# KX1_DB_PWR.net
KiCad netlist of a schematic drawn in Altium Designer
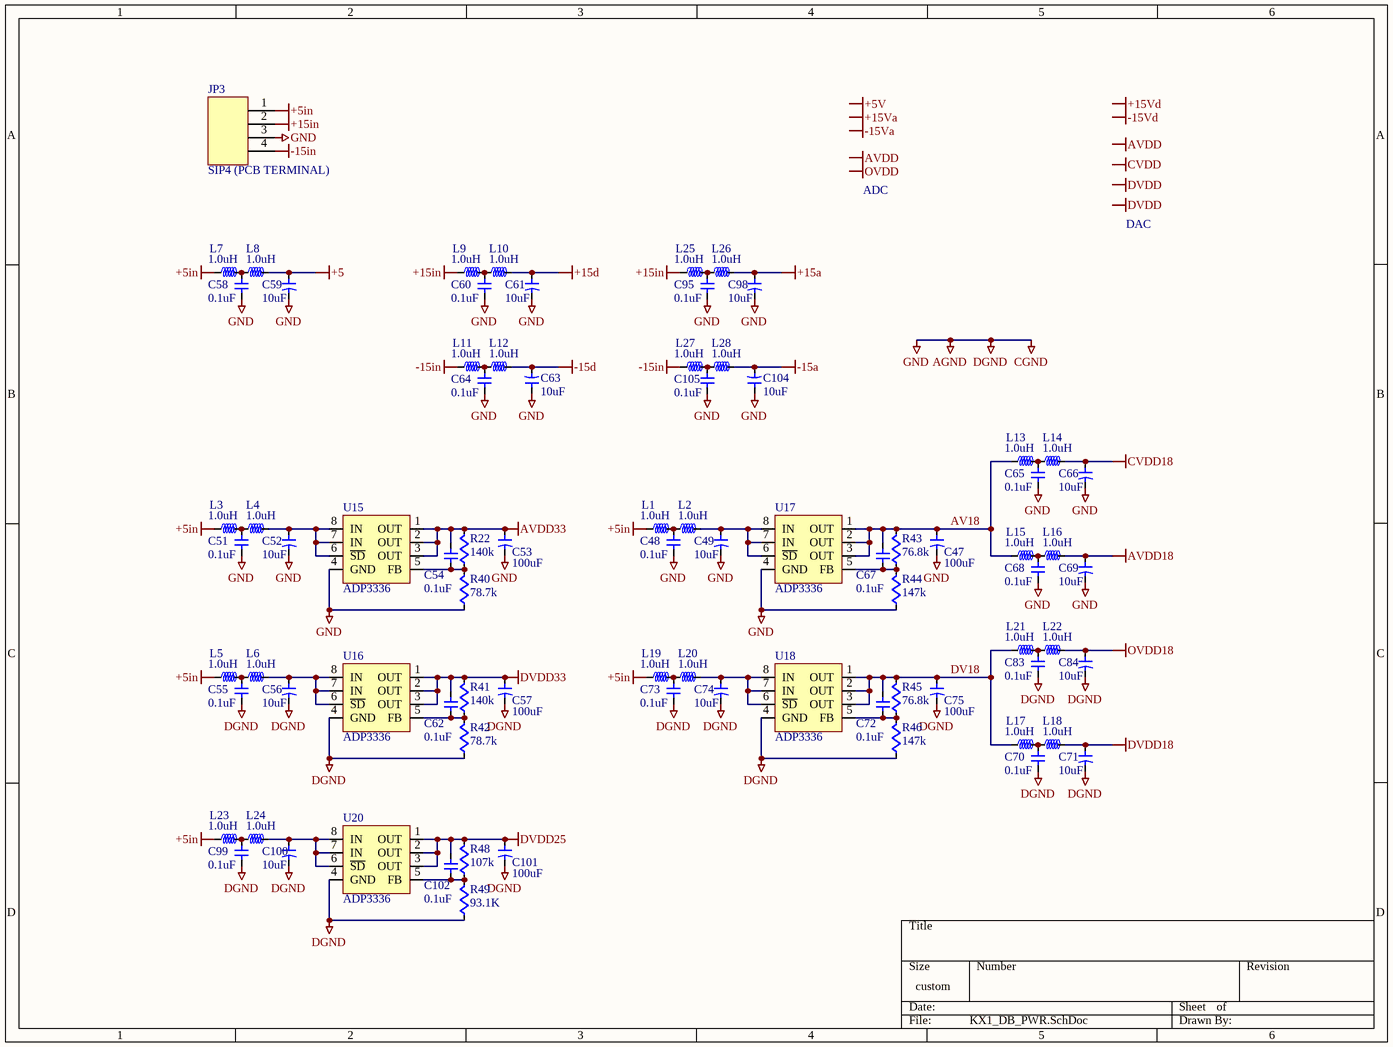
[diagram p0: KX1_DB_PWR.SchDoc]

(export (version "E")
  (design (tool "Eeschema 10.0.6"))
  (components
    (comp (ref "C47")
      (value "100uF")
      (footprint "1206")
      (description "capacitor")
      (fields
        (field (name "MANUFACTURER") "TDK Corporation")
        (field (name "MANUFACTURER PART NUMBER") "C3216X5R0J107M")
      )
      (libsource (lib "KX1_DB") (part "CAPACITOR_SM"))
    )
    (comp (ref "C48")
      (value "0.1uF")
      (footprint "0603w")
      (description "capacitor")
      (fields
        (field (name "MANUFACTURER") "Kemet")
        (field (name "MANUFACTURER PART NUMBER") "C0603C104K3RACTU")
      )
      (libsource (lib "KX1_DB") (part "CAP_SM"))
    )
    (comp (ref "C49")
      (value "10uF")
      (footprint "1206")
      (description "ELECTROLYTIC capacitor")
      (fields
        (field (name "MANUFACTURER") "Nichicon")
        (field (name "MANUFACTURER PART NUMBER") "F971C106MAA")
      )
      (libsource (lib "KX1_DB") (part "CAPACITOR_SM"))
    )
    (comp (ref "C51")
      (value "0.1uF")
      (footprint "0603w")
      (description "capacitor")
      (fields
        (field (name "MANUFACTURER") "Kemet")
        (field (name "MANUFACTURER PART NUMBER") "C0603C104K3RACTU")
      )
      (libsource (lib "KX1_DB") (part "CAP_SM"))
    )
    (comp (ref "C52")
      (value "10uF")
      (footprint "1206")
      (description "ELECTROLYTIC capacitor")
      (fields
        (field (name "MANUFACTURER") "Nichicon")
        (field (name "MANUFACTURER PART NUMBER") "F971C106MAA")
      )
      (libsource (lib "KX1_DB") (part "CAPACITOR_SM"))
    )
    (comp (ref "C53")
      (value "100uF")
      (footprint "1206")
      (description "capacitor")
      (fields
        (field (name "MANUFACTURER") "TDK Corporation")
        (field (name "MANUFACTURER PART NUMBER") "C3216X5R0J107M")
      )
      (libsource (lib "KX1_DB") (part "CAPACITOR_SM"))
    )
    (comp (ref "C54")
      (value "0.1uF")
      (footprint "0603w")
      (description "capacitor")
      (fields
        (field (name "MANUFACTURER") "Kemet")
        (field (name "MANUFACTURER PART NUMBER") "C0603C104K3RACTU")
      )
      (libsource (lib "KX1_DB") (part "CAP_SM"))
    )
    (comp (ref "C55")
      (value "0.1uF")
      (footprint "0603w")
      (description "capacitor")
      (fields
        (field (name "MANUFACTURER") "Kemet")
        (field (name "MANUFACTURER PART NUMBER") "C0603C104K3RACTU")
      )
      (libsource (lib "KX1_DB") (part "CAP_SM"))
    )
    (comp (ref "C56")
      (value "10uF")
      (footprint "1206")
      (description "ELECTROLYTIC capacitor")
      (fields
        (field (name "MANUFACTURER") "Nichicon")
        (field (name "MANUFACTURER PART NUMBER") "F971C106MAA")
      )
      (libsource (lib "KX1_DB") (part "CAPACITOR_SM"))
    )
    (comp (ref "C57")
      (value "100uF")
      (footprint "1206")
      (description "capacitor")
      (fields
        (field (name "MANUFACTURER") "TDK Corporation")
        (field (name "MANUFACTURER PART NUMBER") "C3216X5R0J107M")
      )
      (libsource (lib "KX1_DB") (part "CAPACITOR_SM"))
    )
    (comp (ref "C58")
      (value "0.1uF")
      (footprint "0603w")
      (description "capacitor")
      (fields
        (field (name "MANUFACTURER") "Kemet")
        (field (name "MANUFACTURER PART NUMBER") "C0603C104K3RACTU")
      )
      (libsource (lib "KX1_DB") (part "CAP_SM"))
    )
    (comp (ref "C59")
      (value "10uF")
      (footprint "1206")
      (description "ELECTROLYTIC capacitor")
      (fields
        (field (name "MANUFACTURER") "Nichicon")
        (field (name "MANUFACTURER PART NUMBER") "F971C106MAA")
      )
      (libsource (lib "KX1_DB") (part "CAPACITOR_SM"))
    )
    (comp (ref "C60")
      (value "0.1uF")
      (footprint "0603w")
      (description "capacitor")
      (fields
        (field (name "MANUFACTURER") "Kemet")
        (field (name "MANUFACTURER PART NUMBER") "C0603C104K3RACTU")
      )
      (libsource (lib "KX1_DB") (part "CAP_SM"))
    )
    (comp (ref "C61")
      (value "10uF")
      (footprint "1206")
      (description "ELECTROLYTIC capacitor")
      (fields
        (field (name "MANUFACTURER") "Nichicon")
        (field (name "MANUFACTURER PART NUMBER") "F971C106MAA")
      )
      (libsource (lib "KX1_DB") (part "CAPACITOR_SM"))
    )
    (comp (ref "C62")
      (value "0.1uF")
      (footprint "0603w")
      (description "capacitor")
      (fields
        (field (name "MANUFACTURER") "Kemet")
        (field (name "MANUFACTURER PART NUMBER") "C0603C104K3RACTU")
      )
      (libsource (lib "KX1_DB") (part "CAP_SM"))
    )
    (comp (ref "C63")
      (value "10uF")
      (footprint "1206")
      (description "ELECTROLYTIC capacitor")
      (fields
        (field (name "MANUFACTURER") "Nichicon")
        (field (name "MANUFACTURER PART NUMBER") "F971C106MAA")
      )
      (libsource (lib "KX1_DB") (part "CAPACITOR_SM"))
    )
    (comp (ref "C64")
      (value "0.1uF")
      (footprint "0603w")
      (description "capacitor")
      (fields
        (field (name "MANUFACTURER") "Kemet")
        (field (name "MANUFACTURER PART NUMBER") "C0603C104K3RACTU")
      )
      (libsource (lib "KX1_DB") (part "CAP_SM"))
    )
    (comp (ref "C65")
      (value "0.1uF")
      (footprint "0603w")
      (description "capacitor")
      (fields
        (field (name "MANUFACTURER") "Kemet")
        (field (name "MANUFACTURER PART NUMBER") "C0603C104K3RACTU")
      )
      (libsource (lib "KX1_DB") (part "CAP_SM"))
    )
    (comp (ref "C66")
      (value "10uF")
      (footprint "1206")
      (description "ELECTROLYTIC capacitor")
      (fields
        (field (name "MANUFACTURER") "Nichicon")
        (field (name "MANUFACTURER PART NUMBER") "F971C106MAA")
      )
      (libsource (lib "KX1_DB") (part "CAPACITOR_SM"))
    )
    (comp (ref "C67")
      (value "0.1uF")
      (footprint "0603w")
      (description "capacitor")
      (fields
        (field (name "MANUFACTURER") "Kemet")
        (field (name "MANUFACTURER PART NUMBER") "C0603C104K3RACTU")
      )
      (libsource (lib "KX1_DB") (part "CAP_SM"))
    )
    (comp (ref "C68")
      (value "0.1uF")
      (footprint "0603w")
      (description "capacitor")
      (fields
        (field (name "MANUFACTURER") "Kemet")
        (field (name "MANUFACTURER PART NUMBER") "C0603C104K3RACTU")
      )
      (libsource (lib "KX1_DB") (part "CAP_SM"))
    )
    (comp (ref "C69")
      (value "10uF")
      (footprint "1206")
      (description "ELECTROLYTIC capacitor")
      (fields
        (field (name "MANUFACTURER") "Nichicon")
        (field (name "MANUFACTURER PART NUMBER") "F971C106MAA")
      )
      (libsource (lib "KX1_DB") (part "CAPACITOR_SM"))
    )
    (comp (ref "C70")
      (value "0.1uF")
      (footprint "0603w")
      (description "capacitor")
      (fields
        (field (name "MANUFACTURER") "Kemet")
        (field (name "MANUFACTURER PART NUMBER") "C0603C104K3RACTU")
      )
      (libsource (lib "KX1_DB") (part "CAP_SM"))
    )
    (comp (ref "C71")
      (value "10uF")
      (footprint "1206")
      (description "ELECTROLYTIC capacitor")
      (fields
        (field (name "MANUFACTURER") "Nichicon")
        (field (name "MANUFACTURER PART NUMBER") "F971C106MAA")
      )
      (libsource (lib "KX1_DB") (part "CAPACITOR_SM"))
    )
    (comp (ref "C72")
      (value "0.1uF")
      (footprint "0603w")
      (description "capacitor")
      (fields
        (field (name "MANUFACTURER") "Kemet")
        (field (name "MANUFACTURER PART NUMBER") "C0603C104K3RACTU")
      )
      (libsource (lib "KX1_DB") (part "CAP_SM"))
    )
    (comp (ref "C73")
      (value "0.1uF")
      (footprint "0603w")
      (description "capacitor")
      (fields
        (field (name "MANUFACTURER") "Kemet")
        (field (name "MANUFACTURER PART NUMBER") "C0603C104K3RACTU")
      )
      (libsource (lib "KX1_DB") (part "CAP_SM"))
    )
    (comp (ref "C74")
      (value "10uF")
      (footprint "1206")
      (description "ELECTROLYTIC capacitor")
      (fields
        (field (name "MANUFACTURER") "Nichicon")
        (field (name "MANUFACTURER PART NUMBER") "F971C106MAA")
      )
      (libsource (lib "KX1_DB") (part "CAPACITOR_SM"))
    )
    (comp (ref "C75")
      (value "100uF")
      (footprint "1206")
      (description "capacitor")
      (fields
        (field (name "MANUFACTURER") "TDK Corporation")
        (field (name "MANUFACTURER PART NUMBER") "C3216X5R0J107M")
      )
      (libsource (lib "KX1_DB") (part "CAPACITOR_SM"))
    )
    (comp (ref "C83")
      (value "0.1uF")
      (footprint "0603w")
      (description "capacitor")
      (fields
        (field (name "MANUFACTURER") "Kemet")
        (field (name "MANUFACTURER PART NUMBER") "C0603C104K3RACTU")
      )
      (libsource (lib "KX1_DB") (part "CAP_SM"))
    )
    (comp (ref "C84")
      (value "10uF")
      (footprint "1206")
      (description "ELECTROLYTIC capacitor")
      (fields
        (field (name "MANUFACTURER") "Nichicon")
        (field (name "MANUFACTURER PART NUMBER") "F971C106MAA")
      )
      (libsource (lib "KX1_DB") (part "CAPACITOR_SM"))
    )
    (comp (ref "C95")
      (value "0.1uF")
      (footprint "0603w")
      (description "capacitor")
      (fields
        (field (name "MANUFACTURER") "Kemet")
        (field (name "MANUFACTURER PART NUMBER") "C0603C104K3RACTU")
      )
      (libsource (lib "KX1_DB") (part "CAP_SM"))
    )
    (comp (ref "C98")
      (value "10uF")
      (footprint "1206")
      (description "ELECTROLYTIC capacitor")
      (fields
        (field (name "MANUFACTURER") "Nichicon")
        (field (name "MANUFACTURER PART NUMBER") "F971C106MAA")
      )
      (libsource (lib "KX1_DB") (part "CAPACITOR_SM"))
    )
    (comp (ref "C99")
      (value "0.1uF")
      (footprint "0603w")
      (description "capacitor")
      (fields
        (field (name "MANUFACTURER") "Kemet")
        (field (name "MANUFACTURER PART NUMBER") "C0603C104K3RACTU")
      )
      (libsource (lib "KX1_DB") (part "CAP_SM"))
    )
    (comp (ref "C100")
      (value "10uF")
      (footprint "1206")
      (description "ELECTROLYTIC capacitor")
      (fields
        (field (name "MANUFACTURER") "Nichicon")
        (field (name "MANUFACTURER PART NUMBER") "F971C106MAA")
      )
      (libsource (lib "KX1_DB") (part "CAPACITOR_SM"))
    )
    (comp (ref "C101")
      (value "100uF")
      (footprint "1206")
      (description "capacitor")
      (fields
        (field (name "MANUFACTURER") "TDK Corporation")
        (field (name "MANUFACTURER PART NUMBER") "C3216X5R0J107M")
      )
      (libsource (lib "KX1_DB") (part "CAPACITOR_SM"))
    )
    (comp (ref "C102")
      (value "0.1uF")
      (footprint "0603w")
      (description "capacitor")
      (fields
        (field (name "MANUFACTURER") "Kemet")
        (field (name "MANUFACTURER PART NUMBER") "C0603C104K3RACTU")
      )
      (libsource (lib "KX1_DB") (part "CAP_SM"))
    )
    (comp (ref "C104")
      (value "10uF")
      (footprint "1206")
      (description "ELECTROLYTIC capacitor")
      (fields
        (field (name "MANUFACTURER") "Nichicon")
        (field (name "MANUFACTURER PART NUMBER") "F971C106MAA")
      )
      (libsource (lib "KX1_DB") (part "CAPACITOR_SM"))
    )
    (comp (ref "C105")
      (value "0.1uF")
      (footprint "0603w")
      (description "capacitor")
      (fields
        (field (name "MANUFACTURER") "Kemet")
        (field (name "MANUFACTURER PART NUMBER") "C0603C104K3RACTU")
      )
      (libsource (lib "KX1_DB") (part "CAP_SM"))
    )
    (comp (ref "JP3")
      (value "SIP4 (PCB TERMINAL)")
      (footprint "SIP4MOLEX")
      (description "4 pin molex connector")
      (fields
        (field (name "MANUFACTURER") "Molex Inc")
        (field (name "MANUFACTURER PART NUMBER") "22-29-2041")
      )
      (libsource (lib "KX1_DB") (part "SIP4 (PCB TERMINAL)"))
    )
    (comp (ref "L1")
      (value "1.0uH")
      (footprint "1210")
      (description "inductor")
      (fields
        (field (name "MANUFACTURER") "Murata Electronics North America")
        (field (name "MANUFACTURER PART NUMBER") "LQH32CN1R0M23L")
      )
      (libsource (lib "KX1_DB") (part "INDUCTOR_SM"))
    )
    (comp (ref "L2")
      (value "1.0uH")
      (footprint "1210")
      (description "inductor")
      (fields
        (field (name "MANUFACTURER") "Murata Electronics North America")
        (field (name "MANUFACTURER PART NUMBER") "LQH32CN1R0M23L")
      )
      (libsource (lib "KX1_DB") (part "INDUCTOR_SM"))
    )
    (comp (ref "L3")
      (value "1.0uH")
      (footprint "0805")
      (description "inductor")
      (fields
        (field (name "MANUFACTURER") "Murata Electronics North America")
        (field (name "MANUFACTURER PART NUMBER") "LQM21FN1R0N00D")
      )
      (libsource (lib "KX1_DB") (part "INDUCTOR_SM"))
    )
    (comp (ref "L4")
      (value "1.0uH")
      (footprint "0805")
      (description "inductor")
      (fields
        (field (name "MANUFACTURER") "Murata Electronics North America")
        (field (name "MANUFACTURER PART NUMBER") "LQM21FN1R0N00D")
      )
      (libsource (lib "KX1_DB") (part "INDUCTOR_SM"))
    )
    (comp (ref "L5")
      (value "1.0uH")
      (footprint "0805")
      (description "inductor")
      (fields
        (field (name "MANUFACTURER") "Murata Electronics North America")
        (field (name "MANUFACTURER PART NUMBER") "LQM21FN1R0N00D")
      )
      (libsource (lib "KX1_DB") (part "INDUCTOR_SM"))
    )
    (comp (ref "L6")
      (value "1.0uH")
      (footprint "0805")
      (description "inductor")
      (fields
        (field (name "MANUFACTURER") "Murata Electronics North America")
        (field (name "MANUFACTURER PART NUMBER") "LQM21FN1R0N00D")
      )
      (libsource (lib "KX1_DB") (part "INDUCTOR_SM"))
    )
    (comp (ref "L7")
      (value "1.0uH")
      (footprint "1210")
      (description "inductor")
      (fields
        (field (name "MANUFACTURER") "Murata Electronics North America")
        (field (name "MANUFACTURER PART NUMBER") "LQH32CN1R0M23L")
      )
      (libsource (lib "KX1_DB") (part "INDUCTOR_SM"))
    )
    (comp (ref "L8")
      (value "1.0uH")
      (footprint "1210")
      (description "inductor")
      (fields
        (field (name "MANUFACTURER") "Murata Electronics North America")
        (field (name "MANUFACTURER PART NUMBER") "LQH32CN1R0M23L")
      )
      (libsource (lib "KX1_DB") (part "INDUCTOR_SM"))
    )
    (comp (ref "L9")
      (value "1.0uH")
      (footprint "1210")
      (description "inductor")
      (fields
        (field (name "MANUFACTURER") "Murata Electronics North America")
        (field (name "MANUFACTURER PART NUMBER") "LQH32CN1R0M23L")
      )
      (libsource (lib "KX1_DB") (part "INDUCTOR_SM"))
    )
    (comp (ref "L10")
      (value "1.0uH")
      (footprint "1210")
      (description "inductor")
      (fields
        (field (name "MANUFACTURER") "Murata Electronics North America")
        (field (name "MANUFACTURER PART NUMBER") "LQH32CN1R0M23L")
      )
      (libsource (lib "KX1_DB") (part "INDUCTOR_SM"))
    )
    (comp (ref "L11")
      (value "1.0uH")
      (footprint "1210")
      (description "inductor")
      (fields
        (field (name "MANUFACTURER") "Murata Electronics North America")
        (field (name "MANUFACTURER PART NUMBER") "LQH32CN1R0M23L")
      )
      (libsource (lib "KX1_DB") (part "INDUCTOR_SM"))
    )
    (comp (ref "L12")
      (value "1.0uH")
      (footprint "1210")
      (description "inductor")
      (fields
        (field (name "MANUFACTURER") "Murata Electronics North America")
        (field (name "MANUFACTURER PART NUMBER") "LQH32CN1R0M23L")
      )
      (libsource (lib "KX1_DB") (part "INDUCTOR_SM"))
    )
    (comp (ref "L13")
      (value "1.0uH")
      (footprint "0805")
      (description "inductor")
      (fields
        (field (name "MANUFACTURER") "Murata Electronics North America")
        (field (name "MANUFACTURER PART NUMBER") "LQM21FN1R0N00D")
      )
      (libsource (lib "KX1_DB") (part "INDUCTOR_SM"))
    )
    (comp (ref "L14")
      (value "1.0uH")
      (footprint "0805")
      (description "inductor")
      (fields
        (field (name "MANUFACTURER") "Murata Electronics North America")
        (field (name "MANUFACTURER PART NUMBER") "LQM21FN1R0N00D")
      )
      (libsource (lib "KX1_DB") (part "INDUCTOR_SM"))
    )
    (comp (ref "L15")
      (value "1.0uH")
      (footprint "1210")
      (description "inductor")
      (fields
        (field (name "MANUFACTURER") "Murata Electronics North America")
        (field (name "MANUFACTURER PART NUMBER") "LQH32CN1R0M23L")
      )
      (libsource (lib "KX1_DB") (part "INDUCTOR_SM"))
    )
    (comp (ref "L16")
      (value "1.0uH")
      (footprint "1210")
      (description "inductor")
      (fields
        (field (name "MANUFACTURER") "Murata Electronics North America")
        (field (name "MANUFACTURER PART NUMBER") "LQH32CN1R0M23L")
      )
      (libsource (lib "KX1_DB") (part "INDUCTOR_SM"))
    )
    (comp (ref "L17")
      (value "1.0uH")
      (footprint "0805")
      (description "inductor")
      (fields
        (field (name "MANUFACTURER") "Murata Electronics North America")
        (field (name "MANUFACTURER PART NUMBER") "LQM21FN1R0N00D")
      )
      (libsource (lib "KX1_DB") (part "INDUCTOR_SM"))
    )
    (comp (ref "L18")
      (value "1.0uH")
      (footprint "0805")
      (description "inductor")
      (fields
        (field (name "MANUFACTURER") "Murata Electronics North America")
        (field (name "MANUFACTURER PART NUMBER") "LQM21FN1R0N00D")
      )
      (libsource (lib "KX1_DB") (part "INDUCTOR_SM"))
    )
    (comp (ref "L19")
      (value "1.0uH")
      (footprint "0805")
      (description "inductor")
      (fields
        (field (name "MANUFACTURER") "Murata Electronics North America")
        (field (name "MANUFACTURER PART NUMBER") "LQM21FN1R0N00D")
      )
      (libsource (lib "KX1_DB") (part "INDUCTOR_SM"))
    )
    (comp (ref "L20")
      (value "1.0uH")
      (footprint "0805")
      (description "inductor")
      (fields
        (field (name "MANUFACTURER") "Murata Electronics North America")
        (field (name "MANUFACTURER PART NUMBER") "LQM21FN1R0N00D")
      )
      (libsource (lib "KX1_DB") (part "INDUCTOR_SM"))
    )
    (comp (ref "L21")
      (value "1.0uH")
      (footprint "0805")
      (description "inductor")
      (fields
        (field (name "MANUFACTURER") "Murata Electronics North America")
        (field (name "MANUFACTURER PART NUMBER") "LQM21FN1R0N00D")
      )
      (libsource (lib "KX1_DB") (part "INDUCTOR_SM"))
    )
    (comp (ref "L22")
      (value "1.0uH")
      (footprint "0805")
      (description "inductor")
      (fields
        (field (name "MANUFACTURER") "Murata Electronics North America")
        (field (name "MANUFACTURER PART NUMBER") "LQM21FN1R0N00D")
      )
      (libsource (lib "KX1_DB") (part "INDUCTOR_SM"))
    )
    (comp (ref "L23")
      (value "1.0uH")
      (footprint "0805")
      (description "inductor")
      (fields
        (field (name "MANUFACTURER") "Murata Electronics North America")
        (field (name "MANUFACTURER PART NUMBER") "LQM21FN1R0N00D")
      )
      (libsource (lib "KX1_DB") (part "INDUCTOR_SM"))
    )
    (comp (ref "L24")
      (value "1.0uH")
      (footprint "0805")
      (description "inductor")
      (fields
        (field (name "MANUFACTURER") "Murata Electronics North America")
        (field (name "MANUFACTURER PART NUMBER") "LQM21FN1R0N00D")
      )
      (libsource (lib "KX1_DB") (part "INDUCTOR_SM"))
    )
    (comp (ref "L25")
      (value "1.0uH")
      (footprint "1210")
      (description "inductor")
      (fields
        (field (name "MANUFACTURER") "Murata Electronics North America")
        (field (name "MANUFACTURER PART NUMBER") "LQH32CN1R0M23L")
      )
      (libsource (lib "KX1_DB") (part "INDUCTOR_SM"))
    )
    (comp (ref "L26")
      (value "1.0uH")
      (footprint "1210")
      (description "inductor")
      (fields
        (field (name "MANUFACTURER") "Murata Electronics North America")
        (field (name "MANUFACTURER PART NUMBER") "LQH32CN1R0M23L")
      )
      (libsource (lib "KX1_DB") (part "INDUCTOR_SM"))
    )
    (comp (ref "L27")
      (value "1.0uH")
      (footprint "1210")
      (description "inductor")
      (fields
        (field (name "MANUFACTURER") "Murata Electronics North America")
        (field (name "MANUFACTURER PART NUMBER") "LQH32CN1R0M23L")
      )
      (libsource (lib "KX1_DB") (part "INDUCTOR_SM"))
    )
    (comp (ref "L28")
      (value "1.0uH")
      (footprint "1210")
      (description "inductor")
      (fields
        (field (name "MANUFACTURER") "Murata Electronics North America")
        (field (name "MANUFACTURER PART NUMBER") "LQH32CN1R0M23L")
      )
      (libsource (lib "KX1_DB") (part "INDUCTOR_SM"))
    )
    (comp (ref "R22")
      (value "140k")
      (footprint "0603w")
      (description "resistor")
      (fields
        (field (name "MANUFACTURER") "Yageo")
        (field (name "MANUFACTURER PART NUMBER") "RC0603FR-07140KL")
      )
      (libsource (lib "KX1_DB") (part "RES_SM"))
    )
    (comp (ref "R40")
      (value "78.7k")
      (footprint "0603w")
      (description "resistor")
      (fields
        (field (name "MANUFACTURER") "Yageo")
        (field (name "MANUFACTURER PART NUMBER") "RC0603FR-0778K7L")
      )
      (libsource (lib "KX1_DB") (part "RES_SM"))
    )
    (comp (ref "R41")
      (value "140k")
      (footprint "0603w")
      (description "resistor")
      (fields
        (field (name "MANUFACTURER") "Yageo")
        (field (name "MANUFACTURER PART NUMBER") "RC0603FR-07140KL")
      )
      (libsource (lib "KX1_DB") (part "RES_SM"))
    )
    (comp (ref "R42")
      (value "78.7k")
      (footprint "0603w")
      (description "resistor")
      (fields
        (field (name "MANUFACTURER") "Yageo")
        (field (name "MANUFACTURER PART NUMBER") "RC0603FR-0778K7L")
      )
      (libsource (lib "KX1_DB") (part "RES_SM"))
    )
    (comp (ref "R43")
      (value "76.8k")
      (footprint "0603w")
      (description "resistor")
      (fields
        (field (name "MANUFACTURER") "Yageo")
        (field (name "MANUFACTURER PART NUMBER") "RC0603FR-0776K8L")
      )
      (libsource (lib "KX1_DB") (part "RES_SM"))
    )
    (comp (ref "R44")
      (value "147k")
      (footprint "0603w")
      (description "resistor")
      (fields
        (field (name "MANUFACTURER") "Yageo")
        (field (name "MANUFACTURER PART NUMBER") "RC0603FR-07147KL")
      )
      (libsource (lib "KX1_DB") (part "RES_SM"))
    )
    (comp (ref "R45")
      (value "76.8k")
      (footprint "0603w")
      (description "resistor")
      (fields
        (field (name "MANUFACTURER") "Yageo")
        (field (name "MANUFACTURER PART NUMBER") "RC0603FR-0776K8L")
      )
      (libsource (lib "KX1_DB") (part "RES_SM"))
    )
    (comp (ref "R46")
      (value "147k")
      (footprint "0603w")
      (description "resistor")
      (fields
        (field (name "MANUFACTURER") "Yageo")
        (field (name "MANUFACTURER PART NUMBER") "RC0603FR-07147KL")
      )
      (libsource (lib "KX1_DB") (part "RES_SM"))
    )
    (comp (ref "R48")
      (value "107k")
      (footprint "0603w")
      (description "resistor")
      (fields
        (field (name "MANUFACTURER") "Yageo")
        (field (name "MANUFACTURER PART NUMBER") "RC0603FR-07107KL")
      )
      (libsource (lib "KX1_DB") (part "RES_SM"))
    )
    (comp (ref "R49")
      (value "93.1K")
      (footprint "0603w")
      (description "resistor")
      (fields
        (field (name "MANUFACTURER") "Yageo")
        (field (name "MANUFACTURER PART NUMBER") "RC0603FR-0793K1L")
      )
      (libsource (lib "KX1_DB") (part "RES_SM"))
    )
    (comp (ref "U15")
      (value "ADP3336")
      (footprint "MSOP08")
      (description "regulator")
      (fields
        (field (name "MANUFACTURER") "Analog Devices Inc")
        (field (name "MANUFACTURER PART NUMBER") "ADP3336ARMZ-REEL7")
      )
      (libsource (lib "KX1_DB") (part "ADP3336"))
    )
    (comp (ref "U16")
      (value "ADP3336")
      (footprint "MSOP08")
      (description "regulator")
      (fields
        (field (name "MANUFACTURER") "Analog Devices Inc")
        (field (name "MANUFACTURER PART NUMBER") "ADP3336ARMZ-REEL7")
      )
      (libsource (lib "KX1_DB") (part "ADP3336"))
    )
    (comp (ref "U17")
      (value "ADP3336")
      (footprint "MSOP08")
      (description "regulator")
      (fields
        (field (name "MANUFACTURER") "Analog Devices Inc")
        (field (name "MANUFACTURER PART NUMBER") "ADP3336ARMZ-REEL7")
      )
      (libsource (lib "KX1_DB") (part "ADP3336"))
    )
    (comp (ref "U18")
      (value "ADP3336")
      (footprint "MSOP08")
      (description "regulator")
      (fields
        (field (name "MANUFACTURER") "Analog Devices Inc")
        (field (name "MANUFACTURER PART NUMBER") "ADP3336ARMZ-REEL7")
      )
      (libsource (lib "KX1_DB") (part "ADP3336"))
    )
    (comp (ref "U20")
      (value "ADP3336")
      (footprint "MSOP08")
      (description "regulator")
      (fields
        (field (name "MANUFACTURER") "Analog Devices Inc")
        (field (name "MANUFACTURER PART NUMBER") "ADP3336ARMZ-REEL7")
      )
      (libsource (lib "KX1_DB") (part "ADP3336"))
    )
  )
  (nets
    (net (code "1") (name "+5") (class "Default")
      (node (ref "C59") (pin "1") (pintype "passive"))
      (node (ref "L8") (pin "2") (pintype "passive"))
    )
    (net (code "3") (name "+5in") (class "Default")
      (node (ref "JP3") (pin "1") (pintype "passive"))
      (node (ref "L1") (pin "1") (pintype "passive"))
      (node (ref "L19") (pin "1") (pintype "passive"))
      (node (ref "L23") (pin "1") (pintype "passive"))
      (node (ref "L3") (pin "1") (pintype "passive"))
      (node (ref "L5") (pin "1") (pintype "passive"))
      (node (ref "L7") (pin "1") (pintype "passive"))
    )
    (net (code "6") (name "+15a") (class "Default")
      (node (ref "C98") (pin "1") (pintype "passive"))
      (node (ref "L26") (pin "2") (pintype "passive"))
    )
    (net (code "7") (name "+15d") (class "Default")
      (node (ref "C61") (pin "1") (pintype "passive"))
      (node (ref "L10") (pin "2") (pintype "passive"))
    )
    (net (code "8") (name "+15in") (class "Default")
      (node (ref "JP3") (pin "2") (pintype "passive"))
      (node (ref "L25") (pin "1") (pintype "passive"))
      (node (ref "L9") (pin "1") (pintype "passive"))
    )
    (net (code "11") (name "-15a") (class "Default")
      (node (ref "C104") (pin "2") (pintype "passive"))
      (node (ref "L28") (pin "2") (pintype "passive"))
    )
    (net (code "12") (name "-15d") (class "Default")
      (node (ref "C63") (pin "2") (pintype "passive"))
      (node (ref "L12") (pin "2") (pintype "passive"))
    )
    (net (code "13") (name "-15in") (class "Default")
      (node (ref "JP3") (pin "4") (pintype "passive"))
      (node (ref "L11") (pin "1") (pintype "passive"))
      (node (ref "L27") (pin "1") (pintype "passive"))
    )
    (net (code "14") (name "/AV18") (class "Default")
      (node (ref "C47") (pin "1") (pintype "passive"))
      (node (ref "C67") (pin "1") (pintype "passive"))
      (node (ref "L13") (pin "1") (pintype "passive"))
      (node (ref "L15") (pin "1") (pintype "passive"))
      (node (ref "R43") (pin "2") (pintype "passive"))
      (node (ref "U17") (pin "1") (pinfunction "OUT_1") (pintype "passive"))
      (node (ref "U17") (pin "2") (pinfunction "OUT_2") (pintype "passive"))
      (node (ref "U17") (pin "3") (pinfunction "OUT_3") (pintype "passive"))
    )
    (net (code "15") (name "/DV18") (class "Default")
      (node (ref "C72") (pin "1") (pintype "passive"))
      (node (ref "C75") (pin "1") (pintype "passive"))
      (node (ref "L17") (pin "1") (pintype "passive"))
      (node (ref "L21") (pin "1") (pintype "passive"))
      (node (ref "R45") (pin "2") (pintype "passive"))
      (node (ref "U18") (pin "1") (pinfunction "OUT_1") (pintype "passive"))
      (node (ref "U18") (pin "2") (pinfunction "OUT_2") (pintype "passive"))
      (node (ref "U18") (pin "3") (pinfunction "OUT_3") (pintype "passive"))
    )
    (net (code "16") (name "AGND") (class "Default")
      (node (ref "C100") (pin "2") (pintype "passive"))
      (node (ref "C101") (pin "2") (pintype "passive"))
      (node (ref "C104") (pin "1") (pintype "passive"))
      (node (ref "C105") (pin "2") (pintype "passive"))
      (node (ref "C47") (pin "2") (pintype "passive"))
      (node (ref "C48") (pin "2") (pintype "passive"))
      (node (ref "C49") (pin "2") (pintype "passive"))
      (node (ref "C51") (pin "2") (pintype "passive"))
      (node (ref "C52") (pin "2") (pintype "passive"))
      (node (ref "C53") (pin "2") (pintype "passive"))
      (node (ref "C55") (pin "2") (pintype "passive"))
      (node (ref "C56") (pin "2") (pintype "passive"))
      (node (ref "C57") (pin "2") (pintype "passive"))
      (node (ref "C58") (pin "2") (pintype "passive"))
      (node (ref "C59") (pin "2") (pintype "passive"))
      (node (ref "C60") (pin "2") (pintype "passive"))
      (node (ref "C61") (pin "2") (pintype "passive"))
      (node (ref "C63") (pin "1") (pintype "passive"))
      (node (ref "C64") (pin "2") (pintype "passive"))
      (node (ref "C65") (pin "2") (pintype "passive"))
      (node (ref "C66") (pin "2") (pintype "passive"))
      (node (ref "C68") (pin "2") (pintype "passive"))
      (node (ref "C69") (pin "2") (pintype "passive"))
      (node (ref "C70") (pin "2") (pintype "passive"))
      (node (ref "C71") (pin "2") (pintype "passive"))
      (node (ref "C73") (pin "2") (pintype "passive"))
      (node (ref "C74") (pin "2") (pintype "passive"))
      (node (ref "C75") (pin "2") (pintype "passive"))
      (node (ref "C83") (pin "2") (pintype "passive"))
      (node (ref "C84") (pin "2") (pintype "passive"))
      (node (ref "C95") (pin "2") (pintype "passive"))
      (node (ref "C98") (pin "2") (pintype "passive"))
      (node (ref "C99") (pin "2") (pintype "passive"))
      (node (ref "JP3") (pin "3") (pintype "passive"))
      (node (ref "R40") (pin "1") (pintype "passive"))
      (node (ref "R42") (pin "1") (pintype "passive"))
      (node (ref "R44") (pin "1") (pintype "passive"))
      (node (ref "R46") (pin "1") (pintype "passive"))
      (node (ref "R49") (pin "1") (pintype "passive"))
      (node (ref "U15") (pin "4") (pinfunction "GND_4") (pintype "passive"))
      (node (ref "U16") (pin "4") (pinfunction "GND_4") (pintype "passive"))
      (node (ref "U17") (pin "4") (pinfunction "GND_4") (pintype "passive"))
      (node (ref "U18") (pin "4") (pinfunction "GND_4") (pintype "passive"))
      (node (ref "U20") (pin "4") (pinfunction "GND_4") (pintype "passive"))
    )
    (net (code "18") (name "AVDD18") (class "Default")
      (node (ref "C69") (pin "1") (pintype "passive"))
      (node (ref "L16") (pin "2") (pintype "passive"))
    )
    (net (code "19") (name "AVDD33") (class "Default")
      (node (ref "C53") (pin "1") (pintype "passive"))
      (node (ref "C54") (pin "1") (pintype "passive"))
      (node (ref "R22") (pin "2") (pintype "passive"))
      (node (ref "U15") (pin "1") (pinfunction "OUT_1") (pintype "passive"))
      (node (ref "U15") (pin "2") (pinfunction "OUT_2") (pintype "passive"))
      (node (ref "U15") (pin "3") (pinfunction "OUT_3") (pintype "passive"))
    )
    (net (code "21") (name "CVDD18") (class "Default")
      (node (ref "C66") (pin "1") (pintype "passive"))
      (node (ref "L14") (pin "2") (pintype "passive"))
    )
    (net (code "23") (name "DVDD18") (class "Default")
      (node (ref "C71") (pin "1") (pintype "passive"))
      (node (ref "L18") (pin "2") (pintype "passive"))
    )
    (net (code "24") (name "DVDD25") (class "Default")
      (node (ref "C101") (pin "1") (pintype "passive"))
      (node (ref "C102") (pin "1") (pintype "passive"))
      (node (ref "R48") (pin "2") (pintype "passive"))
      (node (ref "U20") (pin "1") (pinfunction "OUT_1") (pintype "passive"))
      (node (ref "U20") (pin "2") (pinfunction "OUT_2") (pintype "passive"))
      (node (ref "U20") (pin "3") (pinfunction "OUT_3") (pintype "passive"))
    )
    (net (code "25") (name "DVDD33") (class "Default")
      (node (ref "C57") (pin "1") (pintype "passive"))
      (node (ref "C62") (pin "1") (pintype "passive"))
      (node (ref "R41") (pin "2") (pintype "passive"))
      (node (ref "U16") (pin "1") (pinfunction "OUT_1") (pintype "passive"))
      (node (ref "U16") (pin "2") (pinfunction "OUT_2") (pintype "passive"))
      (node (ref "U16") (pin "3") (pinfunction "OUT_3") (pintype "passive"))
    )
    (net (code "26") (name "Net-(C48-Pad1)") (class "Default")
      (node (ref "C48") (pin "1") (pintype "passive"))
      (node (ref "L1") (pin "2") (pintype "passive"))
      (node (ref "L2") (pin "1") (pintype "passive"))
    )
    (net (code "27") (name "Net-(C51-Pad1)") (class "Default")
      (node (ref "C51") (pin "1") (pintype "passive"))
      (node (ref "L3") (pin "2") (pintype "passive"))
      (node (ref "L4") (pin "1") (pintype "passive"))
    )
    (net (code "28") (name "Net-(C55-Pad1)") (class "Default")
      (node (ref "C55") (pin "1") (pintype "passive"))
      (node (ref "L5") (pin "2") (pintype "passive"))
      (node (ref "L6") (pin "1") (pintype "passive"))
    )
    (net (code "29") (name "Net-(C58-Pad1)") (class "Default")
      (node (ref "C58") (pin "1") (pintype "passive"))
      (node (ref "L7") (pin "2") (pintype "passive"))
      (node (ref "L8") (pin "1") (pintype "passive"))
    )
    (net (code "30") (name "Net-(C60-Pad1)") (class "Default")
      (node (ref "C60") (pin "1") (pintype "passive"))
      (node (ref "L10") (pin "1") (pintype "passive"))
      (node (ref "L9") (pin "2") (pintype "passive"))
    )
    (net (code "31") (name "Net-(C64-Pad1)") (class "Default")
      (node (ref "C64") (pin "1") (pintype "passive"))
      (node (ref "L11") (pin "2") (pintype "passive"))
      (node (ref "L12") (pin "1") (pintype "passive"))
    )
    (net (code "32") (name "Net-(C65-Pad1)") (class "Default")
      (node (ref "C65") (pin "1") (pintype "passive"))
      (node (ref "L13") (pin "2") (pintype "passive"))
      (node (ref "L14") (pin "1") (pintype "passive"))
    )
    (net (code "33") (name "Net-(C68-Pad1)") (class "Default")
      (node (ref "C68") (pin "1") (pintype "passive"))
      (node (ref "L15") (pin "2") (pintype "passive"))
      (node (ref "L16") (pin "1") (pintype "passive"))
    )
    (net (code "34") (name "Net-(C70-Pad1)") (class "Default")
      (node (ref "C70") (pin "1") (pintype "passive"))
      (node (ref "L17") (pin "2") (pintype "passive"))
      (node (ref "L18") (pin "1") (pintype "passive"))
    )
    (net (code "35") (name "Net-(C73-Pad1)") (class "Default")
      (node (ref "C73") (pin "1") (pintype "passive"))
      (node (ref "L19") (pin "2") (pintype "passive"))
      (node (ref "L20") (pin "1") (pintype "passive"))
    )
    (net (code "36") (name "Net-(C83-Pad1)") (class "Default")
      (node (ref "C83") (pin "1") (pintype "passive"))
      (node (ref "L21") (pin "2") (pintype "passive"))
      (node (ref "L22") (pin "1") (pintype "passive"))
    )
    (net (code "37") (name "Net-(C95-Pad1)") (class "Default")
      (node (ref "C95") (pin "1") (pintype "passive"))
      (node (ref "L25") (pin "2") (pintype "passive"))
      (node (ref "L26") (pin "1") (pintype "passive"))
    )
    (net (code "38") (name "Net-(C99-Pad1)") (class "Default")
      (node (ref "C99") (pin "1") (pintype "passive"))
      (node (ref "L23") (pin "2") (pintype "passive"))
      (node (ref "L24") (pin "1") (pintype "passive"))
    )
    (net (code "39") (name "Net-(C105-Pad1)") (class "Default")
      (node (ref "C105") (pin "1") (pintype "passive"))
      (node (ref "L27") (pin "2") (pintype "passive"))
      (node (ref "L28") (pin "1") (pintype "passive"))
    )
    (net (code "40") (name "Net-(U15-FB)") (class "Default")
      (node (ref "C54") (pin "2") (pintype "passive"))
      (node (ref "R22") (pin "1") (pintype "passive"))
      (node (ref "R40") (pin "2") (pintype "passive"))
      (node (ref "U15") (pin "5") (pinfunction "FB_5") (pintype "passive"))
    )
    (net (code "41") (name "Net-(U15-~{SD})") (class "Default")
      (node (ref "C52") (pin "1") (pintype "passive"))
      (node (ref "L4") (pin "2") (pintype "passive"))
      (node (ref "U15") (pin "6") (pinfunction "~{SD}_6") (pintype "passive"))
      (node (ref "U15") (pin "7") (pinfunction "IN_7") (pintype "passive"))
      (node (ref "U15") (pin "8") (pinfunction "IN_8") (pintype "passive"))
    )
    (net (code "42") (name "Net-(U16-FB)") (class "Default")
      (node (ref "C62") (pin "2") (pintype "passive"))
      (node (ref "R41") (pin "1") (pintype "passive"))
      (node (ref "R42") (pin "2") (pintype "passive"))
      (node (ref "U16") (pin "5") (pinfunction "FB_5") (pintype "passive"))
    )
    (net (code "43") (name "Net-(U16-~{SD})") (class "Default")
      (node (ref "C56") (pin "1") (pintype "passive"))
      (node (ref "L6") (pin "2") (pintype "passive"))
      (node (ref "U16") (pin "6") (pinfunction "~{SD}_6") (pintype "passive"))
      (node (ref "U16") (pin "7") (pinfunction "IN_7") (pintype "passive"))
      (node (ref "U16") (pin "8") (pinfunction "IN_8") (pintype "passive"))
    )
    (net (code "44") (name "Net-(U17-FB)") (class "Default")
      (node (ref "C67") (pin "2") (pintype "passive"))
      (node (ref "R43") (pin "1") (pintype "passive"))
      (node (ref "R44") (pin "2") (pintype "passive"))
      (node (ref "U17") (pin "5") (pinfunction "FB_5") (pintype "passive"))
    )
    (net (code "45") (name "Net-(U17-~{SD})") (class "Default")
      (node (ref "C49") (pin "1") (pintype "passive"))
      (node (ref "L2") (pin "2") (pintype "passive"))
      (node (ref "U17") (pin "6") (pinfunction "~{SD}_6") (pintype "passive"))
      (node (ref "U17") (pin "7") (pinfunction "IN_7") (pintype "passive"))
      (node (ref "U17") (pin "8") (pinfunction "IN_8") (pintype "passive"))
    )
    (net (code "46") (name "Net-(U18-FB)") (class "Default")
      (node (ref "C72") (pin "2") (pintype "passive"))
      (node (ref "R45") (pin "1") (pintype "passive"))
      (node (ref "R46") (pin "2") (pintype "passive"))
      (node (ref "U18") (pin "5") (pinfunction "FB_5") (pintype "passive"))
    )
    (net (code "47") (name "Net-(U18-~{SD})") (class "Default")
      (node (ref "C74") (pin "1") (pintype "passive"))
      (node (ref "L20") (pin "2") (pintype "passive"))
      (node (ref "U18") (pin "6") (pinfunction "~{SD}_6") (pintype "passive"))
      (node (ref "U18") (pin "7") (pinfunction "IN_7") (pintype "passive"))
      (node (ref "U18") (pin "8") (pinfunction "IN_8") (pintype "passive"))
    )
    (net (code "48") (name "Net-(U20-FB)") (class "Default")
      (node (ref "C102") (pin "2") (pintype "passive"))
      (node (ref "R48") (pin "1") (pintype "passive"))
      (node (ref "R49") (pin "2") (pintype "passive"))
      (node (ref "U20") (pin "5") (pinfunction "FB_5") (pintype "passive"))
    )
    (net (code "49") (name "Net-(U20-~{SD})") (class "Default")
      (node (ref "C100") (pin "1") (pintype "passive"))
      (node (ref "L24") (pin "2") (pintype "passive"))
      (node (ref "U20") (pin "6") (pinfunction "~{SD}_6") (pintype "passive"))
      (node (ref "U20") (pin "7") (pinfunction "IN_7") (pintype "passive"))
      (node (ref "U20") (pin "8") (pinfunction "IN_8") (pintype "passive"))
    )
    (net (code "51") (name "OVDD18") (class "Default")
      (node (ref "C84") (pin "1") (pintype "passive"))
      (node (ref "L22") (pin "2") (pintype "passive"))
    )
  )
)
